# DP83848.net
KiCad netlist of a schematic drawn in Altium Designer
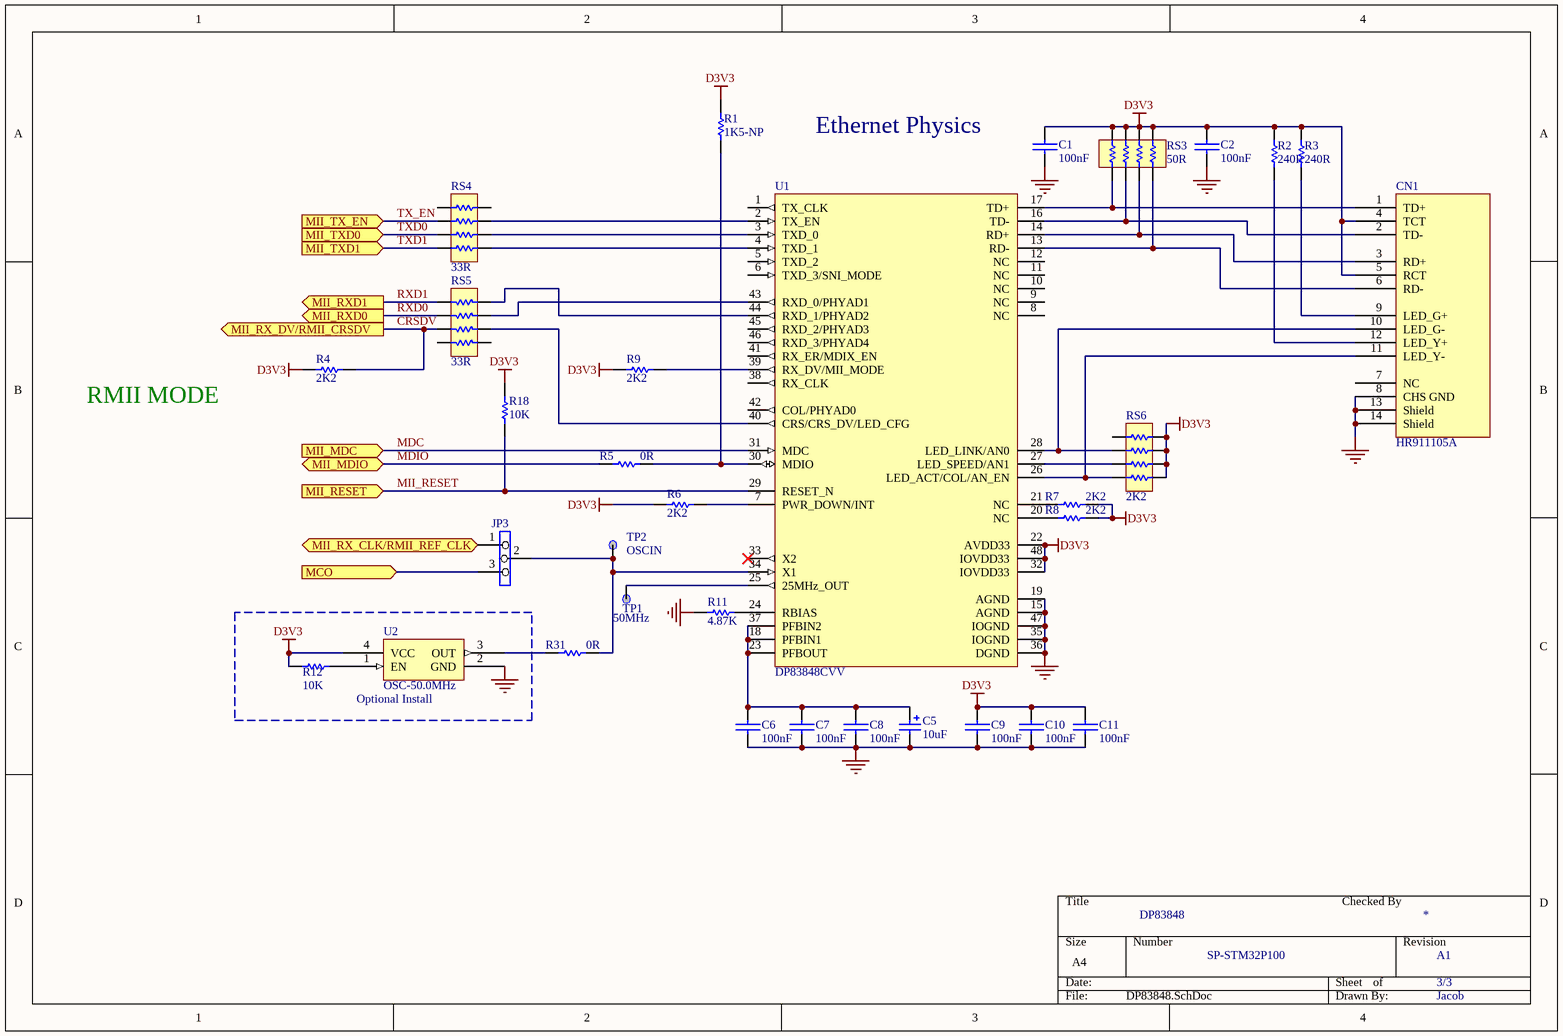
[diagram p0: DP83848.SchDoc]

(export (version "E")
  (design (tool "Eeschema 10.0.6"))
  (components
    (comp (ref "C1")
      (value "100nF")
      (footprint "0603M")
      (description "Capacitor")
      (libsource (lib "*") (part "CAP"))
    )
    (comp (ref "C2")
      (value "100nF")
      (footprint "0603M")
      (description "Capacitor")
      (libsource (lib "*") (part "CAP"))
    )
    (comp (ref "C5")
      (value "10uF")
      (footprint "TAN-A")
      (description "Polarized Capacitor (Radial)")
      (fields (field (name "PUBLISHER") "Altium Limited"))
      (libsource (lib "Miscellaneous Devices") (part "Cap Pol1"))
    )
    (comp (ref "C6")
      (value "100nF")
      (footprint "0603M")
      (description "Capacitor")
      (libsource (lib "*") (part "CAP"))
    )
    (comp (ref "C7")
      (value "100nF")
      (footprint "0603M")
      (description "Capacitor")
      (libsource (lib "*") (part "CAP"))
    )
    (comp (ref "C8")
      (value "100nF")
      (footprint "0603M")
      (description "Capacitor")
      (libsource (lib "*") (part "CAP"))
    )
    (comp (ref "C9")
      (value "100nF")
      (footprint "0603M")
      (description "Capacitor")
      (libsource (lib "*") (part "CAP"))
    )
    (comp (ref "C10")
      (value "100nF")
      (footprint "0603M")
      (description "Capacitor")
      (libsource (lib "*") (part "CAP"))
    )
    (comp (ref "C11")
      (value "100nF")
      (footprint "0603M")
      (description "Capacitor")
      (libsource (lib "*") (part "CAP"))
    )
    (comp (ref "CN1")
      (value "HR911105A")
      (footprint "HR911105A")
      (description "RJ45 From Hanren")
      (libsource (lib "Studio") (part "HR911105A"))
    )
    (comp (ref "JP3")
      (value "~")
      (footprint "HDR1X3/2.00MM")
      (libsource (lib "STR910_SCHLIB") (part "Jumper3"))
    )
    (comp (ref "R1")
      (value "1K5-NP")
      (footprint "0603M")
      (description "Resistor")
      (fields (field (name "PUBLISHER") "Altium Limited"))
      (libsource (lib "Miscellaneous Devices") (part "Res1"))
    )
    (comp (ref "R2")
      (value "240R")
      (footprint "0603M")
      (description "Resistor")
      (fields (field (name "PUBLISHER") "Altium Limited"))
      (libsource (lib "Miscellaneous Devices") (part "Res1"))
    )
    (comp (ref "R3")
      (value "240R")
      (footprint "0603M")
      (description "Resistor")
      (fields (field (name "PUBLISHER") "Altium Limited"))
      (libsource (lib "Miscellaneous Devices") (part "Res1"))
    )
    (comp (ref "R4")
      (value "2K2")
      (footprint "0603M")
      (description "Resistor")
      (fields (field (name "PUBLISHER") "Altium Limited"))
      (libsource (lib "Miscellaneous Devices") (part "Res1"))
    )
    (comp (ref "R5")
      (value "0R")
      (footprint "0603M")
      (description "Resistor")
      (fields (field (name "PUBLISHER") "Altium Limited"))
      (libsource (lib "Miscellaneous Devices") (part "Res1"))
    )
    (comp (ref "R6")
      (value "2K2")
      (footprint "0603M")
      (description "Resistor")
      (fields (field (name "PUBLISHER") "Altium Limited"))
      (libsource (lib "Miscellaneous Devices") (part "Res1"))
    )
    (comp (ref "R7")
      (value "2K2")
      (footprint "0603M")
      (description "Resistor")
      (fields (field (name "PUBLISHER") "Altium Limited"))
      (libsource (lib "Miscellaneous Devices") (part "Res1"))
    )
    (comp (ref "R8")
      (value "2K2")
      (footprint "0603M")
      (description "Resistor")
      (fields (field (name "PUBLISHER") "Altium Limited"))
      (libsource (lib "Miscellaneous Devices") (part "Res1"))
    )
    (comp (ref "R9")
      (value "2K2")
      (footprint "0603M")
      (description "Resistor")
      (fields (field (name "PUBLISHER") "Altium Limited"))
      (libsource (lib "Miscellaneous Devices") (part "Res1"))
    )
    (comp (ref "R11")
      (value "4.87K")
      (footprint "0603M")
      (description "Resistor")
      (fields (field (name "PUBLISHER") "Altium Limited"))
      (libsource (lib "Miscellaneous Devices") (part "Res1"))
    )
    (comp (ref "R12")
      (value "10K")
      (footprint "0603M")
      (description "Resistor")
      (fields (field (name "PUBLISHER") "Altium Limited"))
      (libsource (lib "Miscellaneous Devices") (part "Res1"))
    )
    (comp (ref "R18")
      (value "10K")
      (footprint "0603M")
      (description "Resistor")
      (fields (field (name "PUBLISHER") "Altium Limited"))
      (libsource (lib "Miscellaneous Devices") (part "Res1"))
    )
    (comp (ref "R31")
      (value "0R")
      (footprint "0603M")
      (description "Resistor")
      (fields (field (name "PUBLISHER") "Altium Limited"))
      (libsource (lib "Miscellaneous Devices") (part "Res1"))
    )
    (comp (ref "RS3") (value "50R") (footprint "RES-4B") (libsource (lib "MB784") (part "Resister Array")))
    (comp (ref "RS4") (value "33R") (footprint "RES-4B") (libsource (lib "") (part "Resister Array_1")))
    (comp (ref "RS5") (value "33R") (footprint "RES-4B") (libsource (lib "*") (part "Resister Array")))
    (comp (ref "RS6") (value "2K2") (footprint "RES-4B") (libsource (lib "") (part "Resister Array_1")))
    (comp (ref "TP1") (value "50MHz") (footprint "TP HOLE") (libsource (lib "*") (part "TP")))
    (comp (ref "TP2") (value "OSCIN") (footprint "TP") (libsource (lib "*") (part "TP")))
    (comp (ref "U1") (value "DP83848CVV") (footprint "LQFP48") (libsource (lib "MB784") (part "DP83848CVV")))
    (comp (ref "U2")
      (value "OSC-50.0MHz")
      (footprint "XTAL_5X7")
      (libsource (lib "MB784") (part "SM7745HEV-50.0M"))
    )
  )
  (nets
    (net (code "1") (name "/CRSDV") (class "Default")
      (node (ref "R4") (pin "1") (pinfunction "1_1") (pintype "passive"))
      (node (ref "RS5") (pin "6") (pinfunction "6_6") (pintype "passive"))
    )
    (net (code "2") (name "/MCO") (class "Default") (node (ref "JP3") (pin "3") (pintype "passive")))
    (net (code "3") (name "/MDC") (class "Default")
      (node (ref "U1") (pin "31") (pinfunction "MDC_31") (pintype "input"))
    )
    (net (code "4") (name "/MDIO") (class "Default")
      (node (ref "R5") (pin "1") (pinfunction "1_1") (pintype "passive"))
    )
    (net (code "5") (name "/MII_RESET") (class "Default")
      (node (ref "R18") (pin "1") (pinfunction "1_1") (pintype "passive"))
      (node (ref "U1") (pin "29") (pinfunction "RESET_N_29") (pintype "passive"))
    )
    (net (code "6") (name "/MII_RX_CLK{slash}RMII_REF_CLK") (class "Default")
      (node (ref "JP3") (pin "1") (pintype "passive"))
    )
    (net (code "7") (name "/RXD0") (class "Default")
      (node (ref "RS5") (pin "4") (pinfunction "4_4") (pintype "passive"))
    )
    (net (code "8") (name "/RXD1") (class "Default")
      (node (ref "RS5") (pin "2") (pinfunction "2_2") (pintype "passive"))
    )
    (net (code "9") (name "/TXD0") (class "Default")
      (node (ref "RS4") (pin "4") (pinfunction "4_4") (pintype "passive"))
    )
    (net (code "10") (name "/TXD1") (class "Default")
      (node (ref "RS4") (pin "2") (pinfunction "2_2") (pintype "passive"))
    )
    (net (code "11") (name "/TX_EN") (class "Default")
      (node (ref "RS4") (pin "6") (pinfunction "6_6") (pintype "passive"))
    )
    (net (code "12") (name "D3V3") (class "Default")
      (node (ref "C1") (pin "2") (pinfunction "2_2") (pintype "passive"))
      (node (ref "C10") (pin "2") (pinfunction "2_2") (pintype "passive"))
      (node (ref "C11") (pin "2") (pinfunction "2_2") (pintype "passive"))
      (node (ref "C2") (pin "2") (pinfunction "2_2") (pintype "passive"))
      (node (ref "C9") (pin "1") (pinfunction "1_1") (pintype "passive"))
      (node (ref "CN1") (pin "4") (pinfunction "TCT_4") (pintype "passive"))
      (node (ref "CN1") (pin "5") (pinfunction "RCT_5") (pintype "passive"))
      (node (ref "R1") (pin "2") (pinfunction "2_2") (pintype "passive"))
      (node (ref "R12") (pin "1") (pinfunction "1_1") (pintype "passive"))
      (node (ref "R18") (pin "2") (pinfunction "2_2") (pintype "passive"))
      (node (ref "R2") (pin "2") (pinfunction "2_2") (pintype "passive"))
      (node (ref "R3") (pin "2") (pinfunction "2_2") (pintype "passive"))
      (node (ref "R4") (pin "2") (pinfunction "2_2") (pintype "passive"))
      (node (ref "R6") (pin "1") (pinfunction "1_1") (pintype "passive"))
      (node (ref "R7") (pin "2") (pinfunction "2_2") (pintype "passive"))
      (node (ref "R8") (pin "2") (pinfunction "2_2") (pintype "passive"))
      (node (ref "R9") (pin "2") (pinfunction "2_2") (pintype "passive"))
      (node (ref "RS3") (pin "1") (pinfunction "1_1") (pintype "passive"))
      (node (ref "RS3") (pin "3") (pinfunction "3_3") (pintype "passive"))
      (node (ref "RS3") (pin "5") (pinfunction "5_5") (pintype "passive"))
      (node (ref "RS3") (pin "7") (pinfunction "7_7") (pintype "passive"))
      (node (ref "RS6") (pin "1") (pinfunction "1_1") (pintype "passive"))
      (node (ref "RS6") (pin "3") (pinfunction "3_3") (pintype "passive"))
      (node (ref "RS6") (pin "5") (pinfunction "5_5") (pintype "passive"))
      (node (ref "RS6") (pin "7") (pinfunction "7_7") (pintype "passive"))
      (node (ref "U1") (pin "22") (pinfunction "AVDD33_22") (pintype "passive"))
      (node (ref "U1") (pin "32") (pinfunction "IOVDD33_32") (pintype "passive"))
      (node (ref "U1") (pin "48") (pinfunction "IOVDD33_48") (pintype "passive"))
      (node (ref "U2") (pin "4") (pinfunction "VCC_4") (pintype "passive"))
    )
    (net (code "13") (name "GND") (class "Default")
      (node (ref "C1") (pin "1") (pinfunction "1_1") (pintype "passive"))
      (node (ref "C10") (pin "1") (pinfunction "1_1") (pintype "passive"))
      (node (ref "C11") (pin "1") (pinfunction "1_1") (pintype "passive"))
      (node (ref "C2") (pin "1") (pinfunction "1_1") (pintype "passive"))
      (node (ref "C5") (pin "2") (pinfunction "2_2") (pintype "passive"))
      (node (ref "C6") (pin "2") (pinfunction "2_2") (pintype "passive"))
      (node (ref "C7") (pin "1") (pinfunction "1_1") (pintype "passive"))
      (node (ref "C8") (pin "1") (pinfunction "1_1") (pintype "passive"))
      (node (ref "C9") (pin "2") (pinfunction "2_2") (pintype "passive"))
      (node (ref "CN1") (pin "13") (pinfunction "Shield_13") (pintype "passive"))
      (node (ref "CN1") (pin "14") (pinfunction "Shield_14") (pintype "passive"))
      (node (ref "CN1") (pin "8") (pinfunction "CHS_GND_8") (pintype "passive"))
      (node (ref "R11") (pin "1") (pinfunction "1_1") (pintype "passive"))
      (node (ref "U1") (pin "15") (pinfunction "AGND_15") (pintype "passive"))
      (node (ref "U1") (pin "19") (pinfunction "AGND_19") (pintype "passive"))
      (node (ref "U1") (pin "35") (pinfunction "IOGND_35") (pintype "passive"))
      (node (ref "U1") (pin "36") (pinfunction "DGND_36") (pintype "passive"))
      (node (ref "U1") (pin "47") (pinfunction "IOGND_47") (pintype "passive"))
      (node (ref "U2") (pin "2") (pinfunction "GND_2") (pintype "passive"))
    )
    (net (code "14") (name "Net-(CN1-LED_G+)") (class "Default")
      (node (ref "CN1") (pin "9") (pinfunction "LED_G+_9") (pintype "passive"))
      (node (ref "R3") (pin "1") (pinfunction "1_1") (pintype "passive"))
    )
    (net (code "15") (name "Net-(CN1-LED_G-)") (class "Default")
      (node (ref "CN1") (pin "10") (pinfunction "LED_G-_10") (pintype "passive"))
      (node (ref "RS6") (pin "6") (pinfunction "6_6") (pintype "passive"))
      (node (ref "U1") (pin "28") (pinfunction "LED_LINK/AN0_28") (pintype "passive"))
    )
    (net (code "16") (name "Net-(CN1-LED_Y+)") (class "Default")
      (node (ref "CN1") (pin "12") (pinfunction "LED_Y+_12") (pintype "passive"))
      (node (ref "R2") (pin "1") (pinfunction "1_1") (pintype "passive"))
    )
    (net (code "17") (name "Net-(CN1-LED_Y-)") (class "Default")
      (node (ref "CN1") (pin "11") (pinfunction "LED_Y-_11") (pintype "passive"))
      (node (ref "RS6") (pin "2") (pinfunction "2_2") (pintype "passive"))
      (node (ref "U1") (pin "26") (pinfunction "LED_ACT/COL/AN_EN_26") (pintype "passive"))
    )
    (net (code "18") (name "Net-(CN1-RD+)") (class "Default")
      (node (ref "CN1") (pin "3") (pinfunction "RD+_3") (pintype "passive"))
      (node (ref "RS3") (pin "4") (pinfunction "4_4") (pintype "passive"))
      (node (ref "U1") (pin "14") (pinfunction "RD+_14") (pintype "passive"))
    )
    (net (code "19") (name "Net-(CN1-RD-)") (class "Default")
      (node (ref "CN1") (pin "6") (pinfunction "RD-_6") (pintype "passive"))
      (node (ref "RS3") (pin "2") (pinfunction "2_2") (pintype "passive"))
      (node (ref "U1") (pin "13") (pinfunction "RD-_13") (pintype "passive"))
    )
    (net (code "20") (name "Net-(CN1-TD+)") (class "Default")
      (node (ref "CN1") (pin "1") (pinfunction "TD+_1") (pintype "passive"))
      (node (ref "RS3") (pin "8") (pinfunction "8_8") (pintype "passive"))
      (node (ref "U1") (pin "17") (pinfunction "TD+_17") (pintype "passive"))
    )
    (net (code "21") (name "Net-(CN1-TD-)") (class "Default")
      (node (ref "CN1") (pin "2") (pinfunction "TD-_2") (pintype "passive"))
      (node (ref "RS3") (pin "6") (pinfunction "6_6") (pintype "passive"))
      (node (ref "U1") (pin "16") (pinfunction "TD-_16") (pintype "passive"))
    )
    (net (code "22") (name "Net-(R7-Pad1)") (class "Default")
      (node (ref "R7") (pin "1") (pinfunction "1_1") (pintype "passive"))
      (node (ref "U1") (pin "21") (pinfunction "NC_21") (pintype "passive"))
    )
    (net (code "23") (name "Net-(R8-Pad1)") (class "Default")
      (node (ref "R8") (pin "1") (pinfunction "1_1") (pintype "passive"))
      (node (ref "U1") (pin "20") (pinfunction "NC_20") (pintype "passive"))
    )
    (net (code "24") (name "Net-(U1-25MHz_OUT)") (class "Default")
      (node (ref "TP1") (pin "1") (pinfunction "1_1") (pintype "passive"))
      (node (ref "U1") (pin "25") (pinfunction "25MHz_OUT_25") (pintype "output"))
    )
    (net (code "25") (name "Net-(U1-CRS{slash}CRS_DV{slash}LED_CFG)") (class "Default")
      (node (ref "RS5") (pin "5") (pinfunction "5_5") (pintype "passive"))
      (node (ref "U1") (pin "40") (pinfunction "CRS/CRS_DV/LED_CFG_40") (pintype "output"))
    )
    (net (code "26") (name "Net-(U1-LED_SPEED{slash}AN1)") (class "Default")
      (node (ref "RS6") (pin "4") (pinfunction "4_4") (pintype "passive"))
      (node (ref "U1") (pin "27") (pinfunction "LED_SPEED/AN1_27") (pintype "passive"))
    )
    (net (code "27") (name "Net-(U1-MDIO)") (class "Default")
      (node (ref "R1") (pin "1") (pinfunction "1_1") (pintype "passive"))
      (node (ref "R5") (pin "2") (pinfunction "2_2") (pintype "passive"))
      (node (ref "U1") (pin "30") (pinfunction "MDIO_30") (pintype "bidirectional"))
    )
    (net (code "28") (name "Net-(U1-PFBIN1)") (class "Default")
      (node (ref "C5") (pin "1") (pinfunction "1_1") (pintype "passive"))
      (node (ref "C6") (pin "1") (pinfunction "1_1") (pintype "passive"))
      (node (ref "C7") (pin "2") (pinfunction "2_2") (pintype "passive"))
      (node (ref "C8") (pin "2") (pinfunction "2_2") (pintype "passive"))
      (node (ref "U1") (pin "18") (pinfunction "PFBIN1_18") (pintype "passive"))
      (node (ref "U1") (pin "23") (pinfunction "PFBOUT_23") (pintype "passive"))
      (node (ref "U1") (pin "37") (pinfunction "PFBIN2_37") (pintype "passive"))
    )
    (net (code "29") (name "Net-(U1-PWR_DOWN{slash}INT)") (class "Default")
      (node (ref "R6") (pin "2") (pinfunction "2_2") (pintype "passive"))
      (node (ref "U1") (pin "7") (pinfunction "PWR_DOWN/INT_7") (pintype "passive"))
    )
    (net (code "30") (name "Net-(U1-RBIAS)") (class "Default")
      (node (ref "R11") (pin "2") (pinfunction "2_2") (pintype "passive"))
      (node (ref "U1") (pin "24") (pinfunction "RBIAS_24") (pintype "passive"))
    )
    (net (code "31") (name "Net-(U1-RXD_0{slash}PHYAD1)") (class "Default")
      (node (ref "RS5") (pin "3") (pinfunction "3_3") (pintype "passive"))
      (node (ref "U1") (pin "43") (pinfunction "RXD_0/PHYAD1_43") (pintype "output"))
    )
    (net (code "32") (name "Net-(U1-RXD_1{slash}PHYAD2)") (class "Default")
      (node (ref "RS5") (pin "1") (pinfunction "1_1") (pintype "passive"))
      (node (ref "U1") (pin "44") (pinfunction "RXD_1/PHYAD2_44") (pintype "output"))
    )
    (net (code "33") (name "Net-(U1-RX_DV{slash}MII_MODE)") (class "Default")
      (node (ref "R9") (pin "1") (pinfunction "1_1") (pintype "passive"))
      (node (ref "U1") (pin "39") (pinfunction "RX_DV/MII_MODE_39") (pintype "output"))
    )
    (net (code "34") (name "Net-(U1-TXD_0)") (class "Default")
      (node (ref "RS4") (pin "3") (pinfunction "3_3") (pintype "passive"))
      (node (ref "U1") (pin "3") (pinfunction "TXD_0_3") (pintype "input"))
    )
    (net (code "35") (name "Net-(U1-TXD_1)") (class "Default")
      (node (ref "RS4") (pin "1") (pinfunction "1_1") (pintype "passive"))
      (node (ref "U1") (pin "4") (pinfunction "TXD_1_4") (pintype "input"))
    )
    (net (code "36") (name "Net-(U1-TX_EN)") (class "Default")
      (node (ref "RS4") (pin "5") (pinfunction "5_5") (pintype "passive"))
      (node (ref "U1") (pin "2") (pinfunction "TX_EN_2") (pintype "input"))
    )
    (net (code "37") (name "Net-(U1-X1)") (class "Default")
      (node (ref "JP3") (pin "2") (pintype "passive"))
      (node (ref "R31") (pin "2") (pinfunction "2_2") (pintype "passive"))
      (node (ref "TP2") (pin "1") (pinfunction "1_1") (pintype "passive"))
      (node (ref "U1") (pin "34") (pinfunction "X1_34") (pintype "input"))
    )
    (net (code "38") (name "Net-(U2-EN)") (class "Default")
      (node (ref "R12") (pin "2") (pinfunction "2_2") (pintype "passive"))
      (node (ref "U2") (pin "1") (pinfunction "EN_1") (pintype "input"))
    )
    (net (code "39") (name "Net-(U2-OUT)") (class "Default")
      (node (ref "R31") (pin "1") (pinfunction "1_1") (pintype "passive"))
      (node (ref "U2") (pin "3") (pinfunction "OUT_3") (pintype "output"))
    )
    (net (code "40") (name "unconnected-(CN1-NC-Pad7)") (class "Default")
      (node (ref "CN1") (pin "7") (pinfunction "NC_7") (pintype "passive"))
    )
    (net (code "41") (name "unconnected-(RS4-Pad7)") (class "Default")
      (node (ref "RS4") (pin "7") (pinfunction "7_7") (pintype "passive"))
    )
    (net (code "42") (name "unconnected-(RS4-Pad8)") (class "Default")
      (node (ref "RS4") (pin "8") (pinfunction "8_8") (pintype "passive"))
    )
    (net (code "43") (name "unconnected-(RS5-Pad7)") (class "Default")
      (node (ref "RS5") (pin "7") (pinfunction "7_7") (pintype "passive"))
    )
    (net (code "44") (name "unconnected-(RS5-Pad8)") (class "Default")
      (node (ref "RS5") (pin "8") (pinfunction "8_8") (pintype "passive"))
    )
    (net (code "45") (name "unconnected-(RS6-Pad8)") (class "Default")
      (node (ref "RS6") (pin "8") (pinfunction "8_8") (pintype "passive"))
    )
    (net (code "46") (name "unconnected-(U1-COL{slash}PHYAD0-Pad42)") (class "Default")
      (node (ref "U1") (pin "42") (pinfunction "COL/PHYAD0_42") (pintype "output"))
    )
    (net (code "47") (name "unconnected-(U1-NC-Pad8)") (class "Default")
      (node (ref "U1") (pin "8") (pinfunction "NC_8") (pintype "passive"))
    )
    (net (code "48") (name "unconnected-(U1-NC-Pad9)") (class "Default")
      (node (ref "U1") (pin "9") (pinfunction "NC_9") (pintype "passive"))
    )
    (net (code "49") (name "unconnected-(U1-NC-Pad10)") (class "Default")
      (node (ref "U1") (pin "10") (pinfunction "NC_10") (pintype "passive"))
    )
    (net (code "50") (name "unconnected-(U1-NC-Pad11)") (class "Default")
      (node (ref "U1") (pin "11") (pinfunction "NC_11") (pintype "passive"))
    )
    (net (code "51") (name "unconnected-(U1-NC-Pad12)") (class "Default")
      (node (ref "U1") (pin "12") (pinfunction "NC_12") (pintype "passive"))
    )
    (net (code "52") (name "unconnected-(U1-RXD_2{slash}PHYAD3-Pad45)") (class "Default")
      (node (ref "U1") (pin "45") (pinfunction "RXD_2/PHYAD3_45") (pintype "output"))
    )
    (net (code "53") (name "unconnected-(U1-RXD_3{slash}PHYAD4-Pad46)") (class "Default")
      (node (ref "U1") (pin "46") (pinfunction "RXD_3/PHYAD4_46") (pintype "output"))
    )
    (net (code "54") (name "unconnected-(U1-RX_CLK-Pad38)") (class "Default")
      (node (ref "U1") (pin "38") (pinfunction "RX_CLK_38") (pintype "output"))
    )
    (net (code "55") (name "unconnected-(U1-RX_ER{slash}MDIX_EN-Pad41)") (class "Default")
      (node (ref "U1") (pin "41") (pinfunction "RX_ER/MDIX_EN_41") (pintype "output"))
    )
    (net (code "56") (name "unconnected-(U1-TXD_2-Pad5)") (class "Default")
      (node (ref "U1") (pin "5") (pinfunction "TXD_2_5") (pintype "input"))
    )
    (net (code "57") (name "unconnected-(U1-TXD_3{slash}SNI_MODE-Pad6)") (class "Default")
      (node (ref "U1") (pin "6") (pinfunction "TXD_3/SNI_MODE_6") (pintype "input"))
    )
    (net (code "58") (name "unconnected-(U1-TX_CLK-Pad1)") (class "Default")
      (node (ref "U1") (pin "1") (pinfunction "TX_CLK_1") (pintype "output"))
    )
    (net (code "59") (name "unconnected-(U1-X2-Pad33)") (class "Default")
      (node (ref "U1") (pin "33") (pinfunction "X2_33") (pintype "output+no_connect"))
    )
  )
)
